# TEC_driver.net
KiCad netlist of a schematic drawn in Altium Designer
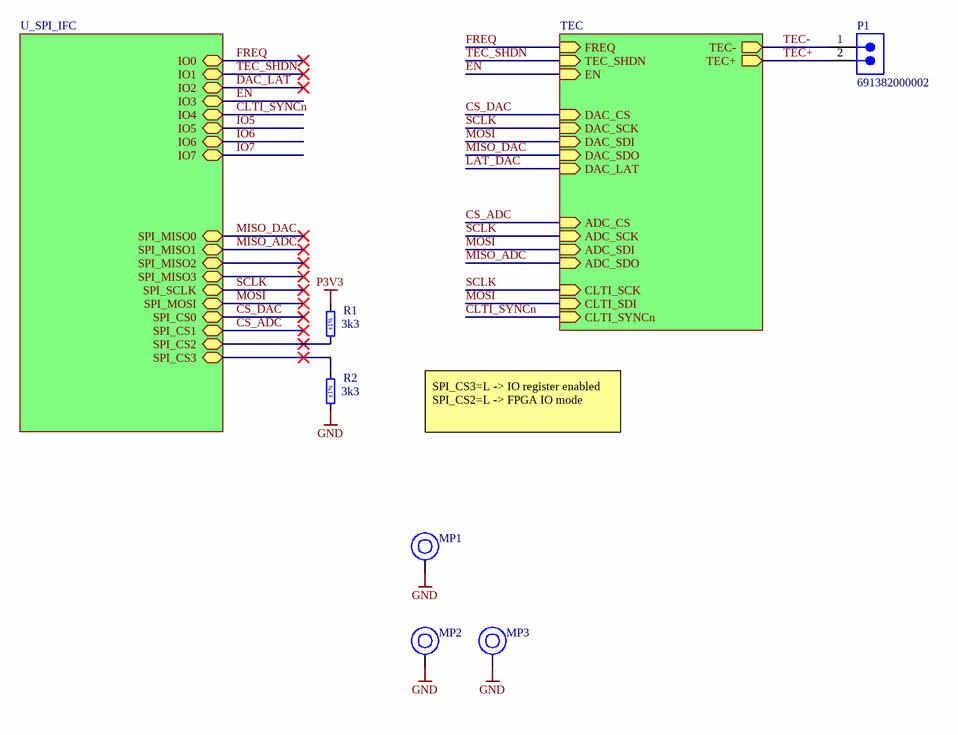
[diagram p0: TEC_driver.SchDoc]

(export (version "E")
  (design (tool "Eeschema 10.0.6"))
  (components
    (comp (ref "MP1")
      (value "M1.6 x 3mm")
      (footprint "97730306330")
      (description "WA-SMSI SMT Steel Spacer with internal Thread Bottom closed, OD 3.3mm, M1.6 x 3mm")
      (fields
        (field (name "MANUFACTURER PART NUMBER") "97730306330R")
        (field (name "MANUFACTURER") "Wurth Elektronik")
      )
      (libsource (lib "Altium_WA-SMSI (rev22a)") (part "97730306330R"))
    )
    (comp (ref "MP2")
      (value "M1.6 x 3mm")
      (footprint "97730306330")
      (description "WA-SMSI SMT Steel Spacer with internal Thread Bottom closed, OD 3.3mm, M1.6 x 3mm")
      (fields
        (field (name "MANUFACTURER PART NUMBER") "97730306330R")
        (field (name "MANUFACTURER") "Wurth Elektronik")
      )
      (libsource (lib "Altium_WA-SMSI (rev22a)") (part "97730306330R"))
    )
    (comp (ref "MP3")
      (value "M1.6 x 3mm")
      (footprint "97730306330")
      (description "WA-SMSI SMT Steel Spacer with internal Thread Bottom closed, OD 3.3mm, M1.6 x 3mm")
      (fields
        (field (name "MANUFACTURER PART NUMBER") "97730306330R")
        (field (name "MANUFACTURER") "Wurth Elektronik")
      )
      (libsource (lib "Altium_WA-SMSI (rev22a)") (part "97730306330R"))
    )
    (comp (ref "P1")
      (value "691382000002")
      (footprint "691382000002")
      (description "WR-TBL Series 382 Vertical PCB Header, THT, pitch 2.5mm, 02p")
      (fields (field (name "MANUFACTURER") "Wurth Elektronik"))
      (libsource (lib "Altium_WR-TBL_Pluggable Connector (rev25d)") (part "691382000002"))
    )
    (comp (ref "R1")
      (value "3k3")
      (footprint "RESC1005X40N")
      (description "Resistor - 1%")
      (fields
        (field (name "TOLERANCE") "±1%")
        (field (name "PART NUMBER") "R0402_3K3_1%_0.0625W_100PPM")
        (field (name "POWER") "0.0625W")
        (field (name "AUTHOR") "CERN DEM JLC")
      )
      (libsource (lib "Resistors") (part "Resistor - 1%"))
    )
    (comp (ref "R2")
      (value "3k3")
      (footprint "RESC1005X40N")
      (description "Resistor - 1%")
      (fields
        (field (name "TOLERANCE") "±1%")
        (field (name "PART NUMBER") "R0402_3K3_1%_0.0625W_100PPM")
        (field (name "POWER") "0.0625W")
        (field (name "AUTHOR") "CERN DEM JLC")
      )
      (libsource (lib "Resistors") (part "Resistor - 1%"))
    )
  )
  (nets
    (net (code "15") (name "/SPI_CS2") (class "Default")
      (node (ref "R1") (pin "2") (pinfunction "2_2") (pintype "passive"))
    )
    (net (code "16") (name "/SPI_CS3") (class "Default")
      (node (ref "R2") (pin "1") (pinfunction "1_1") (pintype "passive"))
    )
    (net (code "19") (name "/TEC+") (class "Default")
      (node (ref "P1") (pin "2") (pinfunction "2_2") (pintype "passive"))
    )
    (net (code "20") (name "/TEC-") (class "Default")
      (node (ref "P1") (pin "1") (pinfunction "1_1") (pintype "passive"))
    )
    (net (code "22") (name "GND") (class "Default")
      (node (ref "MP1") (pin "1") (pinfunction "1_1") (pintype "passive"))
      (node (ref "MP2") (pin "1") (pinfunction "1_1") (pintype "passive"))
      (node (ref "MP3") (pin "1") (pinfunction "1_1") (pintype "passive"))
      (node (ref "R2") (pin "2") (pinfunction "2_2") (pintype "passive"))
    )
    (net (code "23") (name "P3V3") (class "Default")
      (node (ref "R1") (pin "1") (pinfunction "1_1") (pintype "passive"))
    )
  )
)
